# Continuity_Tester.net
KiCad netlist of a schematic drawn in EAGLE
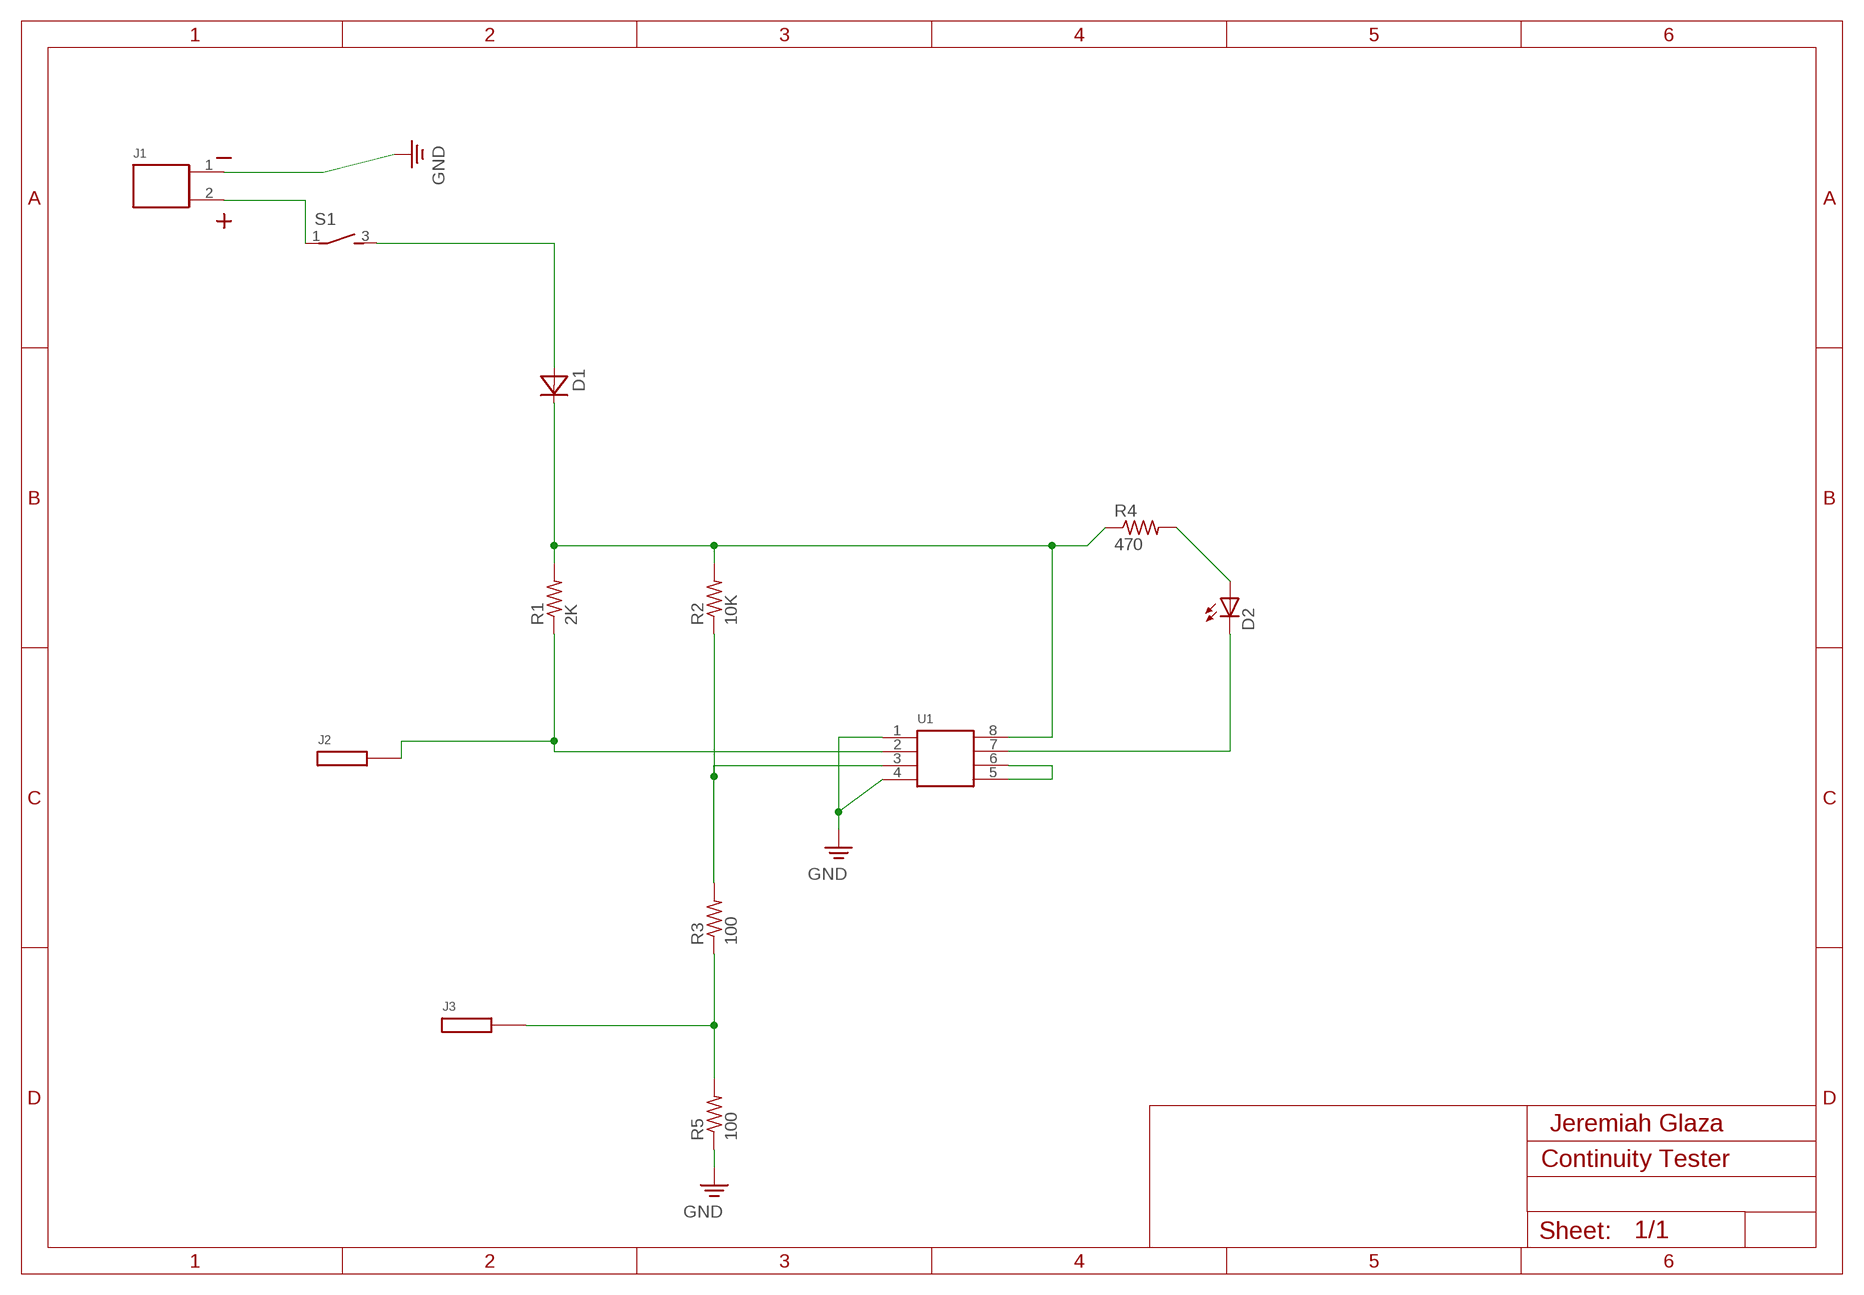
[diagram p0: schematic, sheet 1]

(export (version "E")
  (design (tool "Eeschema 10.0.6"))
  (components
    (comp (ref "D1")
      (value "DIODE")
      (footprint "eagle-import:DIODE-FOOT")
      (libsource (lib "eagle-import") (part "DIODE"))
    )
    (comp (ref "D2")
      (value "LED")
      (footprint "eagle-import:LED-FOOT")
      (libsource (lib "eagle-import") (part "LED"))
    )
    (comp (ref "J1")
      (value "POWER")
      (footprint "eagle-import:POWER-FOOT")
      (libsource (lib "eagle-import") (part "POWER"))
    )
    (comp (ref "J2")
      (value "ALLIGATORCLIP")
      (footprint "eagle-import:ALLIGATORCLIP-FOOT")
      (libsource (lib "eagle-import") (part "ALLIGATORCLIP"))
    )
    (comp (ref "J3")
      (value "ALLIGATORCLIP")
      (footprint "eagle-import:ALLIGATORCLIP-FOOT")
      (libsource (lib "eagle-import") (part "ALLIGATORCLIP"))
    )
    (comp (ref "R1")
      (value "2K")
      (footprint "eagle-import:RES-FOOT")
      (libsource (lib "eagle-import") (part "RES"))
    )
    (comp (ref "R2")
      (value "10K")
      (footprint "eagle-import:RES-FOOT")
      (libsource (lib "eagle-import") (part "RES"))
    )
    (comp (ref "R3")
      (value "100")
      (footprint "eagle-import:RES-FOOT")
      (libsource (lib "eagle-import") (part "RES"))
    )
    (comp (ref "R4")
      (value "470")
      (footprint "eagle-import:RES-FOOT")
      (libsource (lib "eagle-import") (part "RES"))
    )
    (comp (ref "R5")
      (value "100")
      (footprint "eagle-import:RES-FOOT")
      (libsource (lib "eagle-import") (part "RES"))
    )
    (comp (ref "S1")
      (value "SWITCH")
      (footprint "eagle-import:SWITCH-FOOT")
      (libsource (lib "eagle-import") (part "SWITCH"))
    )
    (comp (ref "U1")
      (value "LM311M")
      (footprint "eagle-import:LM311M-FOOT")
      (libsource (lib "eagle-import") (part "LM311M"))
    )
  )
  (nets
    (net (code "1") (name "GND") (class "Default")
      (node (ref "J1") (pin "1") (pinfunction "1_1") (pintype "bidirectional"))
      (node (ref "R5") (pin "1") (pinfunction "1_1") (pintype "passive"))
      (node (ref "U1") (pin "1") (pinfunction "1_1") (pintype "bidirectional"))
      (node (ref "U1") (pin "4") (pinfunction "4_4") (pintype "bidirectional"))
    )
    (net (code "2") (name "Net-(D1-PadA)") (class "Default")
      (node (ref "D1") (pin "A") (pinfunction "A_A") (pintype "passive"))
      (node (ref "S1") (pin "3") (pinfunction "3_3") (pintype "passive"))
    )
    (net (code "3") (name "Net-(D1-PadC)") (class "Default")
      (node (ref "D1") (pin "C") (pinfunction "C_C") (pintype "passive"))
      (node (ref "R1") (pin "2") (pinfunction "2_2") (pintype "passive"))
      (node (ref "R2") (pin "2") (pinfunction "2_2") (pintype "passive"))
      (node (ref "R4") (pin "1") (pinfunction "1_1") (pintype "passive"))
      (node (ref "U1") (pin "8") (pinfunction "8_8") (pintype "bidirectional"))
    )
    (net (code "4") (name "Net-(D2-PadA)") (class "Default")
      (node (ref "D2") (pin "A") (pinfunction "A_A") (pintype "passive"))
      (node (ref "R4") (pin "2") (pinfunction "2_2") (pintype "passive"))
    )
    (net (code "5") (name "Net-(D2-PadC)") (class "Default")
      (node (ref "D2") (pin "C") (pinfunction "C_C") (pintype "passive"))
      (node (ref "U1") (pin "7") (pinfunction "7_7") (pintype "bidirectional"))
    )
    (net (code "6") (name "Net-(J1-Pad2)") (class "Default")
      (node (ref "J1") (pin "2") (pinfunction "2_2") (pintype "bidirectional"))
      (node (ref "S1") (pin "1") (pinfunction "1_1") (pintype "passive"))
    )
    (net (code "7") (name "Net-(J2-Pad1)") (class "Default")
      (node (ref "J2") (pin "1") (pinfunction "1_1") (pintype "bidirectional"))
      (node (ref "R1") (pin "1") (pinfunction "1_1") (pintype "passive"))
      (node (ref "U1") (pin "2") (pinfunction "2_2") (pintype "bidirectional"))
    )
    (net (code "8") (name "Net-(J3-Pad1)") (class "Default")
      (node (ref "J3") (pin "1") (pinfunction "1_1") (pintype "bidirectional"))
      (node (ref "R3") (pin "1") (pinfunction "1_1") (pintype "passive"))
      (node (ref "R5") (pin "2") (pinfunction "2_2") (pintype "passive"))
    )
    (net (code "9") (name "Net-(R2-Pad1)") (class "Default")
      (node (ref "R2") (pin "1") (pinfunction "1_1") (pintype "passive"))
      (node (ref "R3") (pin "2") (pinfunction "2_2") (pintype "passive"))
      (node (ref "U1") (pin "3") (pinfunction "3_3") (pintype "bidirectional"))
    )
    (net (code "10") (name "Net-(U1-Pad5)") (class "Default")
      (node (ref "U1") (pin "5") (pinfunction "5_5") (pintype "bidirectional"))
      (node (ref "U1") (pin "6") (pinfunction "6_6") (pintype "bidirectional"))
    )
  )
)
